# SingleLed.net
KiCad netlist of a schematic drawn in EAGLE
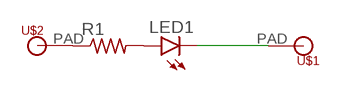
[diagram p0: schematic, sheet 1]

(export (version "E")
  (design (tool "Eeschema 10.0.6"))
  (components
    (comp (ref "LED1")
      (value "LED5MM")
      (footprint "eagle-import:LED5MM")
      (libsource (lib "eagle-import") (part "LED5MM"))
    )
    (comp (ref "R1")
      (value "R-US_0204/7")
      (footprint "eagle-import:0204_7")
      (libsource (lib "eagle-import") (part "R-US_0204/7"))
    )
    (comp (ref "U$1")
      (value "MICROBIT_PAD")
      (footprint "eagle-import:MICROBIT_PAD")
      (libsource (lib "eagle-import") (part "MICROBIT_PAD"))
    )
    (comp (ref "U$2")
      (value "MICROBIT_PAD")
      (footprint "eagle-import:MICROBIT_PAD")
      (libsource (lib "eagle-import") (part "MICROBIT_PAD"))
    )
  )
  (nets
    (net (code "1") (name "Net-(LED1-C)") (class "Default")
      (node (ref "LED1") (pin "K") (pinfunction "C_K") (pintype "passive"))
      (node (ref "U$1") (pin "PAD") (pinfunction "P$1_PAD") (pintype "bidirectional"))
    )
    (net (code "2") (name "Net-(LED1-PadA)") (class "Default")
      (node (ref "LED1") (pin "A") (pinfunction "A_A") (pintype "passive"))
      (node (ref "R1") (pin "2") (pinfunction "2_2") (pintype "passive"))
    )
    (net (code "3") (name "Net-(U$2-P$1)") (class "Default")
      (node (ref "R1") (pin "1") (pinfunction "1_1") (pintype "passive"))
      (node (ref "U$2") (pin "PAD") (pinfunction "P$1_PAD") (pintype "bidirectional"))
    )
  )
)
